# carsystem.net
KiCad netlist of a schematic drawn in Altium Designer
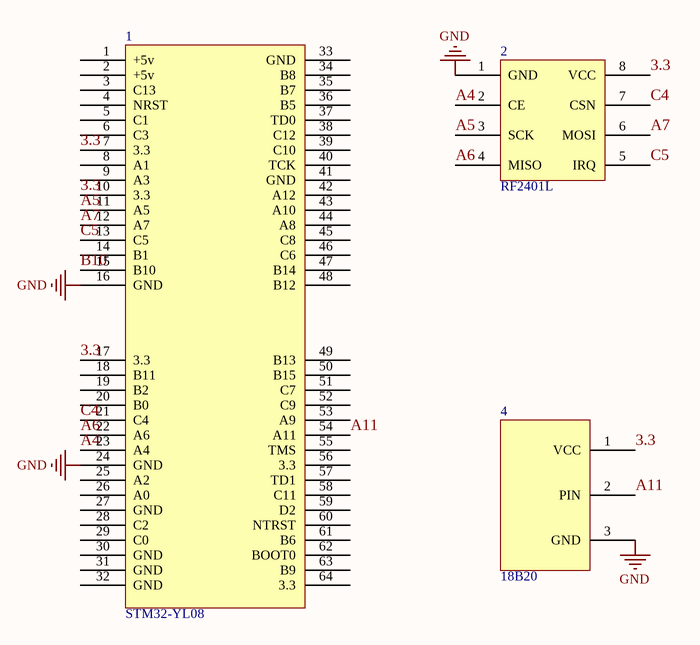
[diagram p0: carsystem.SchDoc]

(export (version "E")
  (design (tool "Eeschema 10.0.6"))
  (components
    (comp (ref "1")
      (value "STM32-YL08")
      (footprint "STM32-YL08")
      (libsource (lib "fengzhuang") (part "STM32-YL08"))
    )
    (comp (ref "2") (value "RF2401L") (footprint "RF2401L") (libsource (lib "fengzhuang") (part "RF2401L")))
    (comp (ref "4") (value "18B20") (footprint "18B20") (libsource (lib "fengzhuang") (part "18B20")))
  )
  (nets
    (net (code "1") (name "/3.3") (class "Default")
      (node (ref "1") (pin "10") (pinfunction "3.3_10") (pintype "passive"))
      (node (ref "1") (pin "17") (pinfunction "3.3_17") (pintype "passive"))
      (node (ref "1") (pin "7") (pinfunction "3.3_7") (pintype "passive"))
      (node (ref "2") (pin "8") (pinfunction "VCC_8") (pintype "passive"))
      (node (ref "4") (pin "1") (pinfunction "VCC_1") (pintype "passive"))
    )
    (net (code "2") (name "/A4") (class "Default")
      (node (ref "1") (pin "23") (pinfunction "A4_23") (pintype "passive"))
      (node (ref "2") (pin "2") (pinfunction "CE_2") (pintype "passive"))
    )
    (net (code "3") (name "/A5") (class "Default")
      (node (ref "1") (pin "11") (pinfunction "A5_11") (pintype "passive"))
      (node (ref "2") (pin "3") (pinfunction "SCK_3") (pintype "passive"))
    )
    (net (code "4") (name "/A6") (class "Default")
      (node (ref "1") (pin "22") (pinfunction "A6_22") (pintype "passive"))
      (node (ref "2") (pin "4") (pinfunction "MISO_4") (pintype "passive"))
    )
    (net (code "5") (name "/A7") (class "Default")
      (node (ref "1") (pin "12") (pinfunction "A7_12") (pintype "passive"))
      (node (ref "2") (pin "6") (pinfunction "MOSI_6") (pintype "passive"))
    )
    (net (code "6") (name "/A11") (class "Default")
      (node (ref "1") (pin "54") (pinfunction "A11_54") (pintype "passive"))
      (node (ref "4") (pin "2") (pinfunction "PIN_2") (pintype "passive"))
    )
    (net (code "7") (name "/B10") (class "Default")
      (node (ref "1") (pin "15") (pinfunction "B10_15") (pintype "passive"))
    )
    (net (code "8") (name "/C4") (class "Default")
      (node (ref "1") (pin "21") (pinfunction "C4_21") (pintype "passive"))
      (node (ref "2") (pin "7") (pinfunction "CSN_7") (pintype "passive"))
    )
    (net (code "9") (name "/C5") (class "Default")
      (node (ref "1") (pin "13") (pinfunction "C5_13") (pintype "passive"))
      (node (ref "2") (pin "5") (pinfunction "IRQ_5") (pintype "passive"))
    )
    (net (code "10") (name "GND") (class "Default")
      (node (ref "1") (pin "16") (pinfunction "GND_16") (pintype "passive"))
      (node (ref "1") (pin "24") (pinfunction "GND_24") (pintype "passive"))
      (node (ref "2") (pin "1") (pinfunction "GND_1") (pintype "passive"))
      (node (ref "4") (pin "3") (pinfunction "GND_3") (pintype "passive"))
    )
    (net (code "11") (name "unconnected-(1-+5v-Pad1)") (class "Default")
      (node (ref "1") (pin "1") (pinfunction "+5v_1") (pintype "passive"))
    )
    (net (code "12") (name "unconnected-(1-+5v-Pad2)") (class "Default")
      (node (ref "1") (pin "2") (pinfunction "+5v_2") (pintype "passive"))
    )
    (net (code "13") (name "unconnected-(1-3.3-Pad56)") (class "Default")
      (node (ref "1") (pin "56") (pinfunction "3.3_56") (pintype "passive"))
    )
    (net (code "14") (name "unconnected-(1-3.3-Pad64)") (class "Default")
      (node (ref "1") (pin "64") (pinfunction "3.3_64") (pintype "passive"))
    )
    (net (code "15") (name "unconnected-(1-A0-Pad26)") (class "Default")
      (node (ref "1") (pin "26") (pinfunction "A0_26") (pintype "passive"))
    )
    (net (code "16") (name "unconnected-(1-A1-Pad8)") (class "Default")
      (node (ref "1") (pin "8") (pinfunction "A1_8") (pintype "passive"))
    )
    (net (code "17") (name "unconnected-(1-A2-Pad25)") (class "Default")
      (node (ref "1") (pin "25") (pinfunction "A2_25") (pintype "passive"))
    )
    (net (code "18") (name "unconnected-(1-A3-Pad9)") (class "Default")
      (node (ref "1") (pin "9") (pinfunction "A3_9") (pintype "passive"))
    )
    (net (code "19") (name "unconnected-(1-A8-Pad44)") (class "Default")
      (node (ref "1") (pin "44") (pinfunction "A8_44") (pintype "passive"))
    )
    (net (code "20") (name "unconnected-(1-A9-Pad53)") (class "Default")
      (node (ref "1") (pin "53") (pinfunction "A9_53") (pintype "passive"))
    )
    (net (code "21") (name "unconnected-(1-A10-Pad43)") (class "Default")
      (node (ref "1") (pin "43") (pinfunction "A10_43") (pintype "passive"))
    )
    (net (code "22") (name "unconnected-(1-A12-Pad42)") (class "Default")
      (node (ref "1") (pin "42") (pinfunction "A12_42") (pintype "passive"))
    )
    (net (code "23") (name "unconnected-(1-B0-Pad20)") (class "Default")
      (node (ref "1") (pin "20") (pinfunction "B0_20") (pintype "passive"))
    )
    (net (code "24") (name "unconnected-(1-B1-Pad14)") (class "Default")
      (node (ref "1") (pin "14") (pinfunction "B1_14") (pintype "passive"))
    )
    (net (code "25") (name "unconnected-(1-B2-Pad19)") (class "Default")
      (node (ref "1") (pin "19") (pinfunction "B2_19") (pintype "passive"))
    )
    (net (code "26") (name "unconnected-(1-B5-Pad36)") (class "Default")
      (node (ref "1") (pin "36") (pinfunction "B5_36") (pintype "passive"))
    )
    (net (code "27") (name "unconnected-(1-B6-Pad61)") (class "Default")
      (node (ref "1") (pin "61") (pinfunction "B6_61") (pintype "passive"))
    )
    (net (code "28") (name "unconnected-(1-B7-Pad35)") (class "Default")
      (node (ref "1") (pin "35") (pinfunction "B7_35") (pintype "passive"))
    )
    (net (code "29") (name "unconnected-(1-B8-Pad34)") (class "Default")
      (node (ref "1") (pin "34") (pinfunction "B8_34") (pintype "passive"))
    )
    (net (code "30") (name "unconnected-(1-B9-Pad63)") (class "Default")
      (node (ref "1") (pin "63") (pinfunction "B9_63") (pintype "passive"))
    )
    (net (code "31") (name "unconnected-(1-B11-Pad18)") (class "Default")
      (node (ref "1") (pin "18") (pinfunction "B11_18") (pintype "passive"))
    )
    (net (code "32") (name "unconnected-(1-B12-Pad48)") (class "Default")
      (node (ref "1") (pin "48") (pinfunction "B12_48") (pintype "passive"))
    )
    (net (code "33") (name "unconnected-(1-B13-Pad49)") (class "Default")
      (node (ref "1") (pin "49") (pinfunction "B13_49") (pintype "passive"))
    )
    (net (code "34") (name "unconnected-(1-B14-Pad47)") (class "Default")
      (node (ref "1") (pin "47") (pinfunction "B14_47") (pintype "passive"))
    )
    (net (code "35") (name "unconnected-(1-B15-Pad50)") (class "Default")
      (node (ref "1") (pin "50") (pinfunction "B15_50") (pintype "passive"))
    )
    (net (code "36") (name "unconnected-(1-BOOT0-Pad62)") (class "Default")
      (node (ref "1") (pin "62") (pinfunction "BOOT0_62") (pintype "passive"))
    )
    (net (code "37") (name "unconnected-(1-C0-Pad29)") (class "Default")
      (node (ref "1") (pin "29") (pinfunction "C0_29") (pintype "passive"))
    )
    (net (code "38") (name "unconnected-(1-C1-Pad5)") (class "Default")
      (node (ref "1") (pin "5") (pinfunction "C1_5") (pintype "passive"))
    )
    (net (code "39") (name "unconnected-(1-C2-Pad28)") (class "Default")
      (node (ref "1") (pin "28") (pinfunction "C2_28") (pintype "passive"))
    )
    (net (code "40") (name "unconnected-(1-C3-Pad6)") (class "Default")
      (node (ref "1") (pin "6") (pinfunction "C3_6") (pintype "passive"))
    )
    (net (code "41") (name "unconnected-(1-C6-Pad46)") (class "Default")
      (node (ref "1") (pin "46") (pinfunction "C6_46") (pintype "passive"))
    )
    (net (code "42") (name "unconnected-(1-C7-Pad51)") (class "Default")
      (node (ref "1") (pin "51") (pinfunction "C7_51") (pintype "passive"))
    )
    (net (code "43") (name "unconnected-(1-C8-Pad45)") (class "Default")
      (node (ref "1") (pin "45") (pinfunction "C8_45") (pintype "passive"))
    )
    (net (code "44") (name "unconnected-(1-C9-Pad52)") (class "Default")
      (node (ref "1") (pin "52") (pinfunction "C9_52") (pintype "passive"))
    )
    (net (code "45") (name "unconnected-(1-C10-Pad39)") (class "Default")
      (node (ref "1") (pin "39") (pinfunction "C10_39") (pintype "passive"))
    )
    (net (code "46") (name "unconnected-(1-C11-Pad58)") (class "Default")
      (node (ref "1") (pin "58") (pinfunction "C11_58") (pintype "passive"))
    )
    (net (code "47") (name "unconnected-(1-C12-Pad38)") (class "Default")
      (node (ref "1") (pin "38") (pinfunction "C12_38") (pintype "passive"))
    )
    (net (code "48") (name "unconnected-(1-C13-Pad3)") (class "Default")
      (node (ref "1") (pin "3") (pinfunction "C13_3") (pintype "passive"))
    )
    (net (code "49") (name "unconnected-(1-D2-Pad59)") (class "Default")
      (node (ref "1") (pin "59") (pinfunction "D2_59") (pintype "passive"))
    )
    (net (code "50") (name "unconnected-(1-GND-Pad27)") (class "Default")
      (node (ref "1") (pin "27") (pinfunction "GND_27") (pintype "passive"))
    )
    (net (code "51") (name "unconnected-(1-GND-Pad30)") (class "Default")
      (node (ref "1") (pin "30") (pinfunction "GND_30") (pintype "passive"))
    )
    (net (code "52") (name "unconnected-(1-GND-Pad31)") (class "Default")
      (node (ref "1") (pin "31") (pinfunction "GND_31") (pintype "passive"))
    )
    (net (code "53") (name "unconnected-(1-GND-Pad32)") (class "Default")
      (node (ref "1") (pin "32") (pinfunction "GND_32") (pintype "passive"))
    )
    (net (code "54") (name "unconnected-(1-GND-Pad33)") (class "Default")
      (node (ref "1") (pin "33") (pinfunction "GND_33") (pintype "passive"))
    )
    (net (code "55") (name "unconnected-(1-GND-Pad41)") (class "Default")
      (node (ref "1") (pin "41") (pinfunction "GND_41") (pintype "passive"))
    )
    (net (code "56") (name "unconnected-(1-NRST-Pad4)") (class "Default")
      (node (ref "1") (pin "4") (pinfunction "NRST_4") (pintype "passive"))
    )
    (net (code "57") (name "unconnected-(1-NTRST-Pad60)") (class "Default")
      (node (ref "1") (pin "60") (pinfunction "NTRST_60") (pintype "passive"))
    )
    (net (code "58") (name "unconnected-(1-TCK-Pad40)") (class "Default")
      (node (ref "1") (pin "40") (pinfunction "TCK_40") (pintype "passive"))
    )
    (net (code "59") (name "unconnected-(1-TD0-Pad37)") (class "Default")
      (node (ref "1") (pin "37") (pinfunction "TD0_37") (pintype "passive"))
    )
    (net (code "60") (name "unconnected-(1-TD1-Pad57)") (class "Default")
      (node (ref "1") (pin "57") (pinfunction "TD1_57") (pintype "passive"))
    )
    (net (code "61") (name "unconnected-(1-TMS-Pad55)") (class "Default")
      (node (ref "1") (pin "55") (pinfunction "TMS_55") (pintype "passive"))
    )
  )
)
